# Lipo_singlecell_charger_mcp73831.net
KiCad netlist of a schematic drawn in EAGLE
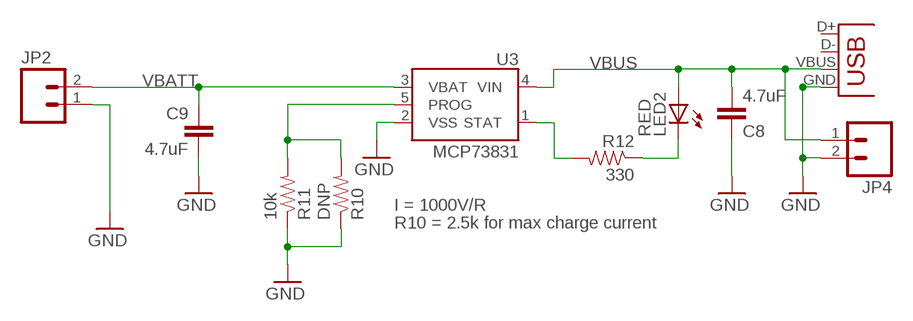
[diagram p0: schematic, sheet 1]

(export (version "E")
  (design (tool "Eeschema 10.0.6"))
  (components
    (comp (ref "C8")
      (value "4.7uF")
      (footprint "eagle-import:0402-CAP")
      (libsource (lib "eagle-import") (part "CAP0402-CAP"))
    )
    (comp (ref "C9")
      (value "4.7uF")
      (footprint "eagle-import:0402-CAP")
      (libsource (lib "eagle-import") (part "CAP0402-CAP"))
    )
    (comp (ref "JP2")
      (value "M02-JST-2MM-SMT")
      (footprint "eagle-import:JST-2-SMD")
      (libsource (lib "eagle-import") (part "M02-JST-2MM-SMT"))
    )
    (comp (ref "JP4")
      (value "M021X02_NO_SILK")
      (footprint "eagle-import:1X02_NO_SILK")
      (libsource (lib "eagle-import") (part "M021X02_NO_SILK"))
    )
    (comp (ref "LED2")
      (value "RED")
      (footprint "eagle-import:LED-0603")
      (libsource (lib "eagle-import") (part "LED0603"))
    )
    (comp (ref "R10")
      (value "DNP")
      (footprint "eagle-import:1_6W-RES")
      (libsource (lib "eagle-import") (part "RESISTORPTH-1/6W"))
    )
    (comp (ref "R11")
      (value "10k")
      (footprint "eagle-import:0402-RES")
      (libsource (lib "eagle-import") (part "RESISTOR0402-RES"))
    )
    (comp (ref "R12")
      (value "330")
      (footprint "eagle-import:0402-RES")
      (libsource (lib "eagle-import") (part "RESISTOR0402-RES"))
    )
    (comp (ref "U3")
      (value "MCP73831")
      (footprint "eagle-import:SOT23-5")
      (libsource (lib "eagle-import") (part "MCP73831"))
    )
    (comp (ref "X1")
      (value "USBSMD")
      (footprint "eagle-import:USB-MINIB")
      (libsource (lib "eagle-import") (part "USBSMD"))
    )
  )
  (nets
    (net (code "1") (name "/VBATT") (class "Default")
      (node (ref "C9") (pin "1") (pinfunction "1_1") (pintype "passive"))
      (node (ref "JP2") (pin "2") (pinfunction "2_2") (pintype "passive"))
      (node (ref "U3") (pin "3") (pinfunction "VBAT_3") (pintype "power_in"))
    )
    (net (code "2") (name "/VBUS") (class "Default")
      (node (ref "C8") (pin "2") (pinfunction "2_2") (pintype "passive"))
      (node (ref "JP4") (pin "1") (pinfunction "1_1") (pintype "passive"))
      (node (ref "LED2") (pin "A") (pinfunction "A_A") (pintype "passive"))
      (node (ref "U3") (pin "4") (pinfunction "VIN_4") (pintype "power_in"))
      (node (ref "X1") (pin "VBUS") (pinfunction "VBUS_VBUS") (pintype "bidirectional"))
    )
    (net (code "3") (name "GND") (class "Default")
      (node (ref "C8") (pin "1") (pinfunction "1_1") (pintype "passive"))
      (node (ref "C9") (pin "2") (pinfunction "2_2") (pintype "passive"))
      (node (ref "JP2") (pin "1") (pinfunction "1_1") (pintype "passive"))
      (node (ref "JP4") (pin "2") (pinfunction "2_2") (pintype "passive"))
      (node (ref "R10") (pin "1") (pinfunction "1_1") (pintype "passive"))
      (node (ref "R11") (pin "1") (pinfunction "1_1") (pintype "passive"))
      (node (ref "U3") (pin "2") (pinfunction "VSS_2") (pintype "power_in"))
      (node (ref "X1") (pin "GND") (pinfunction "GND_GND") (pintype "bidirectional"))
    )
    (net (code "4") (name "Net-(LED2-PadC)") (class "Default")
      (node (ref "LED2") (pin "C") (pinfunction "C_C") (pintype "passive"))
      (node (ref "R12") (pin "1") (pinfunction "1_1") (pintype "passive"))
    )
    (net (code "5") (name "Net-(U3-PROG)") (class "Default")
      (node (ref "R10") (pin "2") (pinfunction "2_2") (pintype "passive"))
      (node (ref "R11") (pin "2") (pinfunction "2_2") (pintype "passive"))
      (node (ref "U3") (pin "5") (pinfunction "PROG_5") (pintype "input"))
    )
    (net (code "6") (name "Net-(U3-STAT)") (class "Default")
      (node (ref "R12") (pin "2") (pinfunction "2_2") (pintype "passive"))
      (node (ref "U3") (pin "1") (pinfunction "STAT_1") (pintype "output"))
    )
    (net (code "7") (name "unconnected-(X1-PadD+)") (class "Default")
      (node (ref "X1") (pin "D+") (pinfunction "D+_D+") (pintype "bidirectional"))
    )
    (net (code "8") (name "unconnected-(X1-PadD-)") (class "Default")
      (node (ref "X1") (pin "D-") (pinfunction "D-_D-") (pintype "bidirectional"))
    )
  )
)
